# alarm.net
KiCad netlist of a schematic drawn in EAGLE
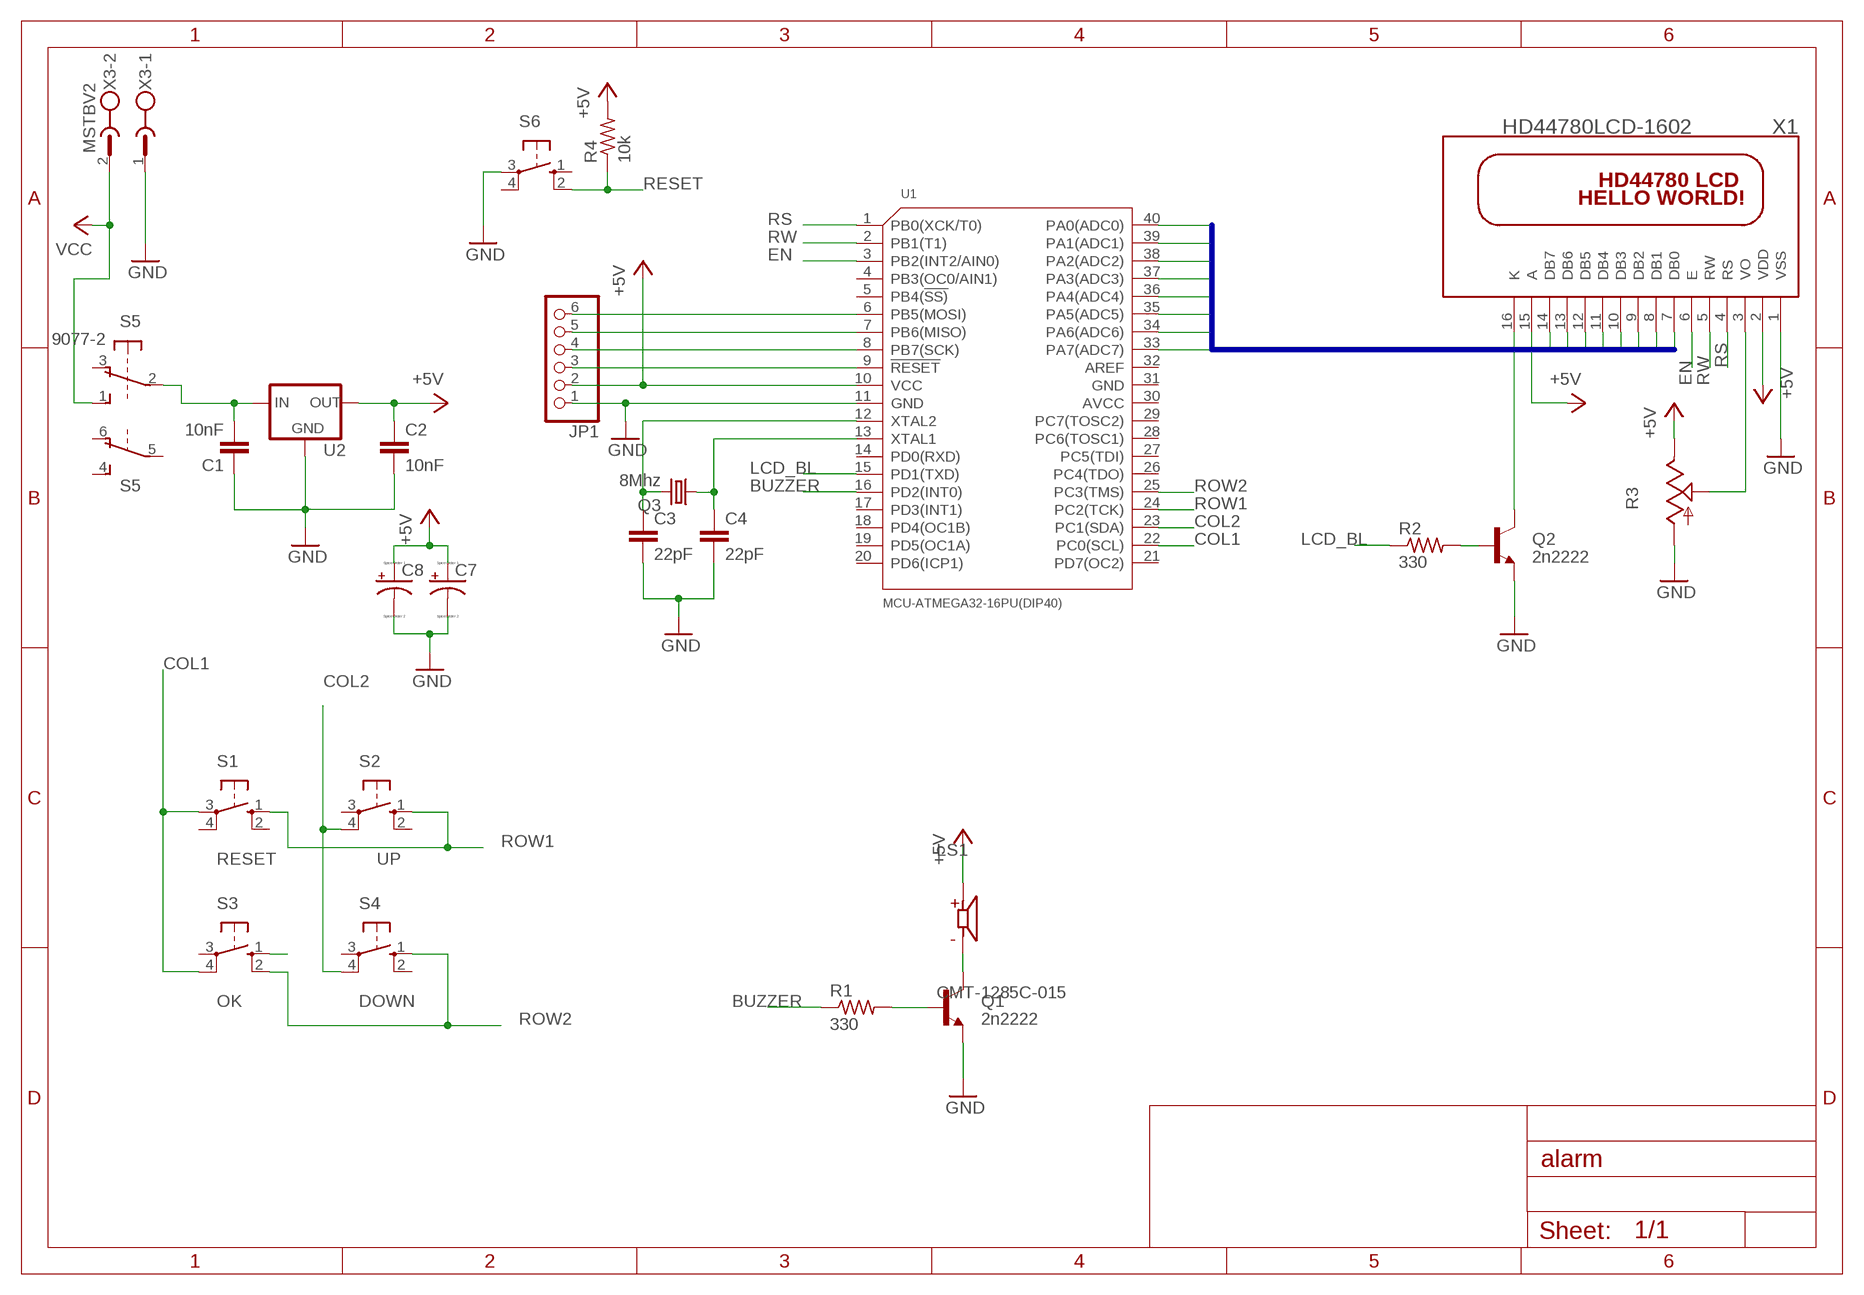
[diagram p0: schematic, sheet 1]

(export (version "E")
  (design (tool "Eeschema 10.0.6"))
  (components
    (comp (ref "C1")
      (value "10nF")
      (footprint "eagle-import:C025-025X050")
      (libsource (lib "eagle-import") (part "C-EU025-025X050"))
    )
    (comp (ref "C2")
      (value "10nF")
      (footprint "eagle-import:C025-025X050")
      (libsource (lib "eagle-import") (part "C-EU025-025X050"))
    )
    (comp (ref "C3")
      (value "22pF")
      (footprint "eagle-import:C025-025X050")
      (libsource (lib "eagle-import") (part "C-EU025-025X050"))
    )
    (comp (ref "C4")
      (value "22pF")
      (footprint "eagle-import:C025-025X050")
      (libsource (lib "eagle-import") (part "C-EU025-025X050"))
    )
    (comp (ref "C7")
      (value "CPOL-USE2.5-6")
      (footprint "eagle-import:E2,5-6")
      (libsource (lib "eagle-import") (part "CPOL-USE2.5-6"))
    )
    (comp (ref "C8")
      (value "CPOL-USE2.5-6")
      (footprint "eagle-import:E2,5-6")
      (libsource (lib "eagle-import") (part "CPOL-USE2.5-6"))
    )
    (comp (ref "JP1")
      (value "PINHD-1X6")
      (footprint "eagle-import:1X06")
      (libsource (lib "eagle-import") (part "PINHD-1X6"))
    )
    (comp (ref "LS1")
      (value "CMT-1285C-015")
      (footprint "eagle-import:CUI_CMT-1285C-015")
      (fields (field (name "MF") "CUI Devices"))
      (libsource (lib "eagle-import") (part "CMT-1285C-015"))
    )
    (comp (ref "Q1")
      (value "2n2222")
      (footprint "eagle-import:TO-92")
      (libsource (lib "eagle-import") (part "TRANSISTOR_NPNP2N2222A"))
    )
    (comp (ref "Q2")
      (value "2n2222")
      (footprint "eagle-import:TO-92")
      (libsource (lib "eagle-import") (part "TRANSISTOR_NPNP2N2222A"))
    )
    (comp (ref "Q3")
      (value "8Mhz")
      (footprint "eagle-import:HC49_S")
      (libsource (lib "eagle-import") (part "CRYSTALHC49S"))
    )
    (comp (ref "R1")
      (value "330")
      (footprint "eagle-import:0207_10")
      (libsource (lib "eagle-import") (part "R-US_0207/10"))
    )
    (comp (ref "R2")
      (value "330")
      (footprint "eagle-import:0207_10")
      (libsource (lib "eagle-import") (part "R-US_0207/10"))
    )
    (comp (ref "R3")
      (value "TRIM_US-RS3")
      (footprint "eagle-import:RS3")
      (libsource (lib "eagle-import") (part "TRIM_US-RS3"))
    )
    (comp (ref "R4")
      (value "10k")
      (footprint "eagle-import:0207_10")
      (libsource (lib "eagle-import") (part "R-US_0207/10"))
    )
    (comp (ref "S1")
      (value "10-XX")
      (footprint "eagle-import:B3F-10XX")
      (fields (field (name "MPN") "B3F-1000"))
      (libsource (lib "eagle-import") (part "10-XX"))
    )
    (comp (ref "S2")
      (value "10-XX")
      (footprint "eagle-import:B3F-10XX")
      (fields (field (name "MPN") "B3F-1000"))
      (libsource (lib "eagle-import") (part "10-XX"))
    )
    (comp (ref "S3")
      (value "10-XX")
      (footprint "eagle-import:B3F-10XX")
      (fields (field (name "MPN") "B3F-1000"))
      (libsource (lib "eagle-import") (part "10-XX"))
    )
    (comp (ref "S4")
      (value "10-XX")
      (footprint "eagle-import:B3F-10XX")
      (fields (field (name "MPN") "B3F-1000"))
      (libsource (lib "eagle-import") (part "10-XX"))
    )
    (comp (ref "S5")
      (value "9077-2")
      (footprint "eagle-import:9077-2")
      (libsource (lib "eagle-import") (part "9077-2"))
    )
    (comp (ref "S6")
      (value "10-XX")
      (footprint "eagle-import:B3F-10XX")
      (fields (field (name "MPN") "B3F-1000"))
      (libsource (lib "eagle-import") (part "10-XX"))
    )
    (comp (ref "U1")
      (value "MCU-ATMEGA32-16PU(DIP40)")
      (footprint "eagle-import:DIP40-2.54-52.3X15.24MM")
      (fields (field (name "MF") "Microchip") (field (name "MP") "ATMEGA32-16PU"))
      (libsource (lib "eagle-import") (part "MCU-ATMEGA32-16PU(DIP40)"))
    )
    (comp (ref "U2")
      (value "78XXL")
      (footprint "eagle-import:78XXL")
      (libsource (lib "eagle-import") (part "78XXL"))
    )
    (comp (ref "X1")
      (value "HD44780LCD-1602")
      (footprint "eagle-import:LCD1602")
      (libsource (lib "eagle-import") (part "HD44780LCD-1602"))
    )
    (comp (ref "X3")
      (value "MSTBV2")
      (footprint "eagle-import:MSTBV2")
      (fields (field (name "MPN") "MSTBV 2,5/2-GF-5.08"))
      (libsource (lib "eagle-import") (part "MSTBV2"))
    )
  )
  (nets
    (net (code "1") (name "+5V") (class "Default")
      (node (ref "C2") (pin "1") (pinfunction "1_1") (pintype "passive"))
      (node (ref "C7") (pin "+") (pinfunction "+_+") (pintype "passive"))
      (node (ref "C8") (pin "+") (pinfunction "+_+") (pintype "passive"))
      (node (ref "JP1") (pin "2") (pinfunction "2_2") (pintype "passive"))
      (node (ref "LS1") (pin "P") (pinfunction "P_P") (pintype "passive"))
      (node (ref "R3") (pin "E") (pinfunction "E_E") (pintype "passive"))
      (node (ref "R4") (pin "2") (pinfunction "2_2") (pintype "passive"))
      (node (ref "U1") (pin "10") (pinfunction "VCC_10") (pintype "bidirectional"))
      (node (ref "U2") (pin "OUT") (pinfunction "OUT_OUT") (pintype "passive"))
      (node (ref "X1") (pin "15") (pinfunction "A_15") (pintype "input"))
      (node (ref "X1") (pin "2") (pinfunction "VDD_2") (pintype "power_in"))
    )
    (net (code "2") (name "/BUZZER") (class "Default")
      (node (ref "R1") (pin "1") (pinfunction "1_1") (pintype "passive"))
      (node (ref "U1") (pin "16") (pinfunction "PD2(INT0)_16") (pintype "bidirectional"))
    )
    (net (code "3") (name "/COL1") (class "Default")
      (node (ref "S1") (pin "3") (pinfunction "P_3") (pintype "passive"))
      (node (ref "S3") (pin "4") (pinfunction "P1_4") (pintype "passive"))
      (node (ref "U1") (pin "22") (pinfunction "PC0(SCL)_22") (pintype "bidirectional"))
    )
    (net (code "4") (name "/COL2") (class "Default")
      (node (ref "S2") (pin "4") (pinfunction "P1_4") (pintype "passive"))
      (node (ref "S4") (pin "4") (pinfunction "P1_4") (pintype "passive"))
      (node (ref "U1") (pin "23") (pinfunction "PC1(SDA)_23") (pintype "bidirectional"))
    )
    (net (code "5") (name "/EN") (class "Default")
      (node (ref "U1") (pin "3") (pinfunction "PB2(INT2/AIN0)_3") (pintype "bidirectional"))
      (node (ref "X1") (pin "6") (pinfunction "E_6") (pintype "input"))
    )
    (net (code "6") (name "/LCD_BL") (class "Default")
      (node (ref "R2") (pin "1") (pinfunction "1_1") (pintype "passive"))
      (node (ref "U1") (pin "15") (pinfunction "PD1(TXD)_15") (pintype "bidirectional"))
    )
    (net (code "7") (name "/PA0") (class "Default")
      (node (ref "U1") (pin "40") (pinfunction "PA0(ADC0)_40") (pintype "bidirectional"))
      (node (ref "X1") (pin "7") (pinfunction "DB0_7") (pintype "bidirectional"))
    )
    (net (code "8") (name "/PA1") (class "Default")
      (node (ref "U1") (pin "39") (pinfunction "PA1(ADC1)_39") (pintype "bidirectional"))
      (node (ref "X1") (pin "8") (pinfunction "DB1_8") (pintype "bidirectional"))
    )
    (net (code "9") (name "/PA2") (class "Default")
      (node (ref "U1") (pin "38") (pinfunction "PA2(ADC2)_38") (pintype "bidirectional"))
      (node (ref "X1") (pin "9") (pinfunction "DB2_9") (pintype "bidirectional"))
    )
    (net (code "10") (name "/PA3") (class "Default")
      (node (ref "U1") (pin "37") (pinfunction "PA3(ADC3)_37") (pintype "bidirectional"))
      (node (ref "X1") (pin "10") (pinfunction "DB3_10") (pintype "bidirectional"))
    )
    (net (code "11") (name "/PA4") (class "Default")
      (node (ref "U1") (pin "36") (pinfunction "PA4(ADC4)_36") (pintype "bidirectional"))
      (node (ref "X1") (pin "11") (pinfunction "DB4_11") (pintype "bidirectional"))
    )
    (net (code "12") (name "/PA5") (class "Default")
      (node (ref "U1") (pin "35") (pinfunction "PA5(ADC5)_35") (pintype "bidirectional"))
      (node (ref "X1") (pin "12") (pinfunction "DB5_12") (pintype "bidirectional"))
    )
    (net (code "13") (name "/PA6") (class "Default")
      (node (ref "U1") (pin "34") (pinfunction "PA6(ADC6)_34") (pintype "bidirectional"))
      (node (ref "X1") (pin "13") (pinfunction "DB6_13") (pintype "bidirectional"))
    )
    (net (code "14") (name "/PA7") (class "Default")
      (node (ref "U1") (pin "33") (pinfunction "PA7(ADC7)_33") (pintype "bidirectional"))
      (node (ref "X1") (pin "14") (pinfunction "DB7_14") (pintype "bidirectional"))
    )
    (net (code "15") (name "/RESET") (class "Default")
      (node (ref "JP1") (pin "3") (pinfunction "3_3") (pintype "passive"))
      (node (ref "R4") (pin "1") (pinfunction "1_1") (pintype "passive"))
      (node (ref "S6") (pin "2") (pinfunction "S1_2") (pintype "passive"))
      (node (ref "U1") (pin "9") (pinfunction "~{RESET}_9") (pintype "bidirectional"))
    )
    (net (code "16") (name "/ROW1") (class "Default")
      (node (ref "S1") (pin "1") (pinfunction "S_1") (pintype "passive"))
      (node (ref "S2") (pin "1") (pinfunction "S_1") (pintype "passive"))
      (node (ref "U1") (pin "24") (pinfunction "PC2(TCK)_24") (pintype "bidirectional"))
    )
    (net (code "17") (name "/ROW2") (class "Default")
      (node (ref "S3") (pin "2") (pinfunction "S1_2") (pintype "passive"))
      (node (ref "S4") (pin "1") (pinfunction "S_1") (pintype "passive"))
      (node (ref "U1") (pin "25") (pinfunction "PC3(TMS)_25") (pintype "bidirectional"))
    )
    (net (code "18") (name "/RS") (class "Default")
      (node (ref "U1") (pin "1") (pinfunction "PB0(XCK/T0)_1") (pintype "bidirectional"))
      (node (ref "X1") (pin "4") (pinfunction "RS_4") (pintype "input"))
    )
    (net (code "19") (name "/RW") (class "Default")
      (node (ref "U1") (pin "2") (pinfunction "PB1(T1)_2") (pintype "bidirectional"))
      (node (ref "X1") (pin "5") (pinfunction "RW_5") (pintype "input"))
    )
    (net (code "20") (name "GND") (class "Default")
      (node (ref "C1") (pin "1") (pinfunction "1_1") (pintype "passive"))
      (node (ref "C2") (pin "2") (pinfunction "2_2") (pintype "passive"))
      (node (ref "C3") (pin "2") (pinfunction "2_2") (pintype "passive"))
      (node (ref "C4") (pin "2") (pinfunction "2_2") (pintype "passive"))
      (node (ref "C7") (pin "-") (pinfunction "-_-") (pintype "passive"))
      (node (ref "C8") (pin "-") (pinfunction "-_-") (pintype "passive"))
      (node (ref "JP1") (pin "1") (pinfunction "1_1") (pintype "passive"))
      (node (ref "Q1") (pin "3") (pinfunction "E_3") (pintype "passive"))
      (node (ref "Q2") (pin "3") (pinfunction "E_3") (pintype "passive"))
      (node (ref "R3") (pin "A") (pinfunction "A_A") (pintype "passive"))
      (node (ref "S6") (pin "3") (pinfunction "P_3") (pintype "passive"))
      (node (ref "U1") (pin "11") (pinfunction "GND_11") (pintype "bidirectional"))
      (node (ref "U2") (pin "GND") (pinfunction "GND_GND") (pintype "input"))
      (node (ref "X1") (pin "1") (pinfunction "VSS_1") (pintype "power_in"))
      (node (ref "X3") (pin "1") (pinfunction "1_1") (pintype "passive"))
    )
    (net (code "21") (name "Net-(Q1-B)") (class "Default")
      (node (ref "Q1") (pin "2") (pinfunction "B_2") (pintype "passive"))
      (node (ref "R1") (pin "2") (pinfunction "2_2") (pintype "passive"))
    )
    (net (code "22") (name "Net-(Q1-C)") (class "Default")
      (node (ref "LS1") (pin "N") (pinfunction "N_N") (pintype "passive"))
      (node (ref "Q1") (pin "1") (pinfunction "C_1") (pintype "passive"))
    )
    (net (code "23") (name "Net-(Q2-B)") (class "Default")
      (node (ref "Q2") (pin "2") (pinfunction "B_2") (pintype "passive"))
      (node (ref "R2") (pin "2") (pinfunction "2_2") (pintype "passive"))
    )
    (net (code "24") (name "Net-(Q2-C)") (class "Default")
      (node (ref "Q2") (pin "1") (pinfunction "C_1") (pintype "passive"))
      (node (ref "X1") (pin "16") (pinfunction "K_16") (pintype "input"))
    )
    (net (code "25") (name "Net-(S5A-P)") (class "Default")
      (node (ref "C1") (pin "2") (pinfunction "2_2") (pintype "passive"))
      (node (ref "S5") (pin "2") (pinfunction "P_2") (pintype "passive"))
      (node (ref "U2") (pin "IN") (pinfunction "IN_IN") (pintype "input"))
    )
    (net (code "26") (name "Net-(U1-PB5(MOSI))") (class "Default")
      (node (ref "JP1") (pin "6") (pinfunction "6_6") (pintype "passive"))
      (node (ref "U1") (pin "6") (pinfunction "PB5(MOSI)_6") (pintype "bidirectional"))
    )
    (net (code "27") (name "Net-(U1-PB6(MISO))") (class "Default")
      (node (ref "JP1") (pin "5") (pinfunction "5_5") (pintype "passive"))
      (node (ref "U1") (pin "7") (pinfunction "PB6(MISO)_7") (pintype "bidirectional"))
    )
    (net (code "28") (name "Net-(U1-PB7(SCK))") (class "Default")
      (node (ref "JP1") (pin "4") (pinfunction "4_4") (pintype "passive"))
      (node (ref "U1") (pin "8") (pinfunction "PB7(SCK)_8") (pintype "bidirectional"))
    )
    (net (code "29") (name "Net-(U1-XTAL1)") (class "Default")
      (node (ref "C4") (pin "1") (pinfunction "1_1") (pintype "passive"))
      (node (ref "Q3") (pin "1") (pinfunction "1_1") (pintype "passive"))
      (node (ref "U1") (pin "13") (pinfunction "XTAL1_13") (pintype "bidirectional"))
    )
    (net (code "30") (name "Net-(U1-XTAL2)") (class "Default")
      (node (ref "C3") (pin "1") (pinfunction "1_1") (pintype "passive"))
      (node (ref "Q3") (pin "2") (pinfunction "2_2") (pintype "passive"))
      (node (ref "U1") (pin "12") (pinfunction "XTAL2_12") (pintype "bidirectional"))
    )
    (net (code "31") (name "Net-(X1-VO)") (class "Default")
      (node (ref "R3") (pin "S") (pinfunction "S_S") (pintype "passive"))
      (node (ref "X1") (pin "3") (pinfunction "VO_3") (pintype "input"))
    )
    (net (code "32") (name "VCC") (class "Default")
      (node (ref "S5") (pin "1") (pinfunction "S_1") (pintype "passive"))
      (node (ref "X3") (pin "2") (pinfunction "1_2") (pintype "passive"))
    )
    (net (code "33") (name "unconnected-(S1-P1-Pad4)") (class "Default")
      (node (ref "S1") (pin "4") (pinfunction "P1_4") (pintype "passive"))
    )
    (net (code "34") (name "unconnected-(S1-S1-Pad2)") (class "Default")
      (node (ref "S1") (pin "2") (pinfunction "S1_2") (pintype "passive"))
    )
    (net (code "35") (name "unconnected-(S2-P-Pad3)") (class "Default")
      (node (ref "S2") (pin "3") (pinfunction "P_3") (pintype "passive"))
    )
    (net (code "36") (name "unconnected-(S2-S1-Pad2)") (class "Default")
      (node (ref "S2") (pin "2") (pinfunction "S1_2") (pintype "passive"))
    )
    (net (code "37") (name "unconnected-(S3-P-Pad3)") (class "Default")
      (node (ref "S3") (pin "3") (pinfunction "P_3") (pintype "passive"))
    )
    (net (code "38") (name "unconnected-(S3-S-Pad1)") (class "Default")
      (node (ref "S3") (pin "1") (pinfunction "S_1") (pintype "passive"))
    )
    (net (code "39") (name "unconnected-(S4-P-Pad3)") (class "Default")
      (node (ref "S4") (pin "3") (pinfunction "P_3") (pintype "passive"))
    )
    (net (code "40") (name "unconnected-(S4-S1-Pad2)") (class "Default")
      (node (ref "S4") (pin "2") (pinfunction "S1_2") (pintype "passive"))
    )
    (net (code "41") (name "unconnected-(S5A-O-Pad3)") (class "Default")
      (node (ref "S5") (pin "3") (pinfunction "O_3") (pintype "passive"))
    )
    (net (code "42") (name "unconnected-(S5B-O-Pad6)") (class "Default")
      (node (ref "S5") (pin "6") (pinfunction "O_6") (pintype "passive"))
    )
    (net (code "43") (name "unconnected-(S5B-P-Pad5)") (class "Default")
      (node (ref "S5") (pin "5") (pinfunction "P_5") (pintype "passive"))
    )
    (net (code "44") (name "unconnected-(S5B-S-Pad4)") (class "Default")
      (node (ref "S5") (pin "4") (pinfunction "S_4") (pintype "passive"))
    )
    (net (code "45") (name "unconnected-(S6-P1-Pad4)") (class "Default")
      (node (ref "S6") (pin "4") (pinfunction "P1_4") (pintype "passive"))
    )
    (net (code "46") (name "unconnected-(S6-S-Pad1)") (class "Default")
      (node (ref "S6") (pin "1") (pinfunction "S_1") (pintype "passive"))
    )
    (net (code "47") (name "unconnected-(U1-AREF-Pad32)") (class "Default")
      (node (ref "U1") (pin "32") (pinfunction "AREF_32") (pintype "bidirectional"))
    )
    (net (code "48") (name "unconnected-(U1-AVCC-Pad30)") (class "Default")
      (node (ref "U1") (pin "30") (pinfunction "AVCC_30") (pintype "bidirectional"))
    )
    (net (code "49") (name "unconnected-(U1-GND-Pad31)") (class "Default")
      (node (ref "U1") (pin "31") (pinfunction "GND_31") (pintype "bidirectional"))
    )
    (net (code "50") (name "unconnected-(U1-PB3(OC0{slash}AIN1)-Pad4)") (class "Default")
      (node (ref "U1") (pin "4") (pinfunction "PB3(OC0/AIN1)_4") (pintype "bidirectional"))
    )
    (net (code "51") (name "unconnected-(U1-PB4(~{SS})-Pad5)") (class "Default")
      (node (ref "U1") (pin "5") (pinfunction "PB4(~{SS})_5") (pintype "bidirectional"))
    )
    (net (code "52") (name "unconnected-(U1-PC4(TDO)-Pad26)") (class "Default")
      (node (ref "U1") (pin "26") (pinfunction "PC4(TDO)_26") (pintype "bidirectional"))
    )
    (net (code "53") (name "unconnected-(U1-PC5(TDI)-Pad27)") (class "Default")
      (node (ref "U1") (pin "27") (pinfunction "PC5(TDI)_27") (pintype "bidirectional"))
    )
    (net (code "54") (name "unconnected-(U1-PC6(TOSC1)-Pad28)") (class "Default")
      (node (ref "U1") (pin "28") (pinfunction "PC6(TOSC1)_28") (pintype "bidirectional"))
    )
    (net (code "55") (name "unconnected-(U1-PC7(TOSC2)-Pad29)") (class "Default")
      (node (ref "U1") (pin "29") (pinfunction "PC7(TOSC2)_29") (pintype "bidirectional"))
    )
    (net (code "56") (name "unconnected-(U1-PD0(RXD)-Pad14)") (class "Default")
      (node (ref "U1") (pin "14") (pinfunction "PD0(RXD)_14") (pintype "bidirectional"))
    )
    (net (code "57") (name "unconnected-(U1-PD3(INT1)-Pad17)") (class "Default")
      (node (ref "U1") (pin "17") (pinfunction "PD3(INT1)_17") (pintype "bidirectional"))
    )
    (net (code "58") (name "unconnected-(U1-PD4(OC1B)-Pad18)") (class "Default")
      (node (ref "U1") (pin "18") (pinfunction "PD4(OC1B)_18") (pintype "bidirectional"))
    )
    (net (code "59") (name "unconnected-(U1-PD5(OC1A)-Pad19)") (class "Default")
      (node (ref "U1") (pin "19") (pinfunction "PD5(OC1A)_19") (pintype "bidirectional"))
    )
    (net (code "60") (name "unconnected-(U1-PD6(ICP1)-Pad20)") (class "Default")
      (node (ref "U1") (pin "20") (pinfunction "PD6(ICP1)_20") (pintype "bidirectional"))
    )
    (net (code "61") (name "unconnected-(U1-PD7(OC2)-Pad21)") (class "Default")
      (node (ref "U1") (pin "21") (pinfunction "PD7(OC2)_21") (pintype "bidirectional"))
    )
  )
)
